# NIBB.net
KiCad netlist of a schematic drawn in EAGLE
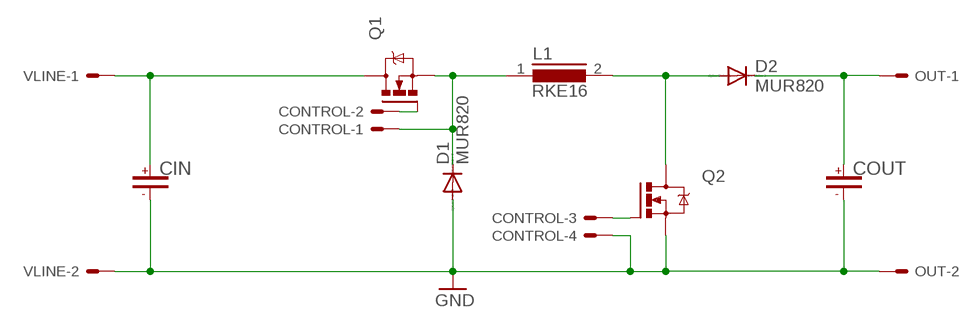
[diagram p0: schematic, sheet 1]

(export (version "E")
  (design (tool "Eeschema 10.0.6"))
  (components
    (comp (ref "CIN")
      (value "CAPP-UF")
      (footprint "eagle-import:20ROUND40P")
      (libsource (lib "eagle-import") (part "CAPP-UF"))
    )
    (comp (ref "CONTROL")
      (value "22-23-2041")
      (footprint "eagle-import:22-23-2041")
      (fields (field (name "MF") "MOLEX"))
      (libsource (lib "eagle-import") (part "22-23-2041"))
    )
    (comp (ref "COUT")
      (value "CAPP-UF")
      (footprint "eagle-import:20ROUND40P")
      (libsource (lib "eagle-import") (part "CAPP-UF"))
    )
    (comp (ref "D1")
      (value "MUR820")
      (footprint "eagle-import:C221B1A")
      (libsource (lib "eagle-import") (part "MUR820"))
    )
    (comp (ref "D2")
      (value "MUR820")
      (footprint "eagle-import:C221B1A")
      (libsource (lib "eagle-import") (part "MUR820"))
    )
    (comp (ref "L1")
      (value "RKE16")
      (footprint "eagle-import:RKE16")
      (libsource (lib "eagle-import") (part "RKE16"))
    )
    (comp (ref "OUT")
      (value "22-23-2021")
      (footprint "eagle-import:22-23-2021")
      (fields (field (name "MF") "MOLEX"))
      (libsource (lib "eagle-import") (part "22-23-2021"))
    )
    (comp (ref "Q1")
      (value "IRF640")
      (footprint "eagle-import:TO220BV")
      (libsource (lib "eagle-import") (part "IRF640"))
    )
    (comp (ref "Q2")
      (value "IRF640")
      (footprint "eagle-import:TO220BV")
      (libsource (lib "eagle-import") (part "IRF640"))
    )
    (comp (ref "VLINE")
      (value "22-23-2021")
      (footprint "eagle-import:22-23-2021")
      (fields (field (name "MF") "MOLEX"))
      (libsource (lib "eagle-import") (part "22-23-2021"))
    )
  )
  (nets
    (net (code "1") (name "GND") (class "Default")
      (node (ref "CIN") (pin "-") (pinfunction "-_-") (pintype "passive"))
      (node (ref "CONTROL") (pin "4") (pinfunction "S_4") (pintype "passive"))
      (node (ref "COUT") (pin "-") (pinfunction "-_-") (pintype "passive"))
      (node (ref "D1") (pin "A") (pinfunction "A_A") (pintype "passive"))
      (node (ref "OUT") (pin "2") (pinfunction "S_2") (pintype "passive"))
      (node (ref "Q2") (pin "S") (pinfunction "S_S") (pintype "passive"))
      (node (ref "VLINE") (pin "2") (pinfunction "S_2") (pintype "passive"))
    )
    (net (code "2") (name "Net-(CONTROLA-S)") (class "Default")
      (node (ref "CONTROL") (pin "1") (pinfunction "S_1") (pintype "passive"))
      (node (ref "D1") (pin "C") (pinfunction "C_C") (pintype "passive"))
      (node (ref "L1") (pin "1") (pinfunction "1_1") (pintype "passive"))
      (node (ref "Q1") (pin "S") (pinfunction "S_S") (pintype "passive"))
    )
    (net (code "3") (name "Net-(CONTROLB-S)") (class "Default")
      (node (ref "CONTROL") (pin "2") (pinfunction "S_2") (pintype "passive"))
      (node (ref "Q1") (pin "G") (pinfunction "G_G") (pintype "passive"))
    )
    (net (code "4") (name "Net-(CONTROLC-S)") (class "Default")
      (node (ref "CONTROL") (pin "3") (pinfunction "S_3") (pintype "passive"))
      (node (ref "Q2") (pin "G") (pinfunction "G_G") (pintype "passive"))
    )
    (net (code "5") (name "Net-(D2-PadA)") (class "Default")
      (node (ref "D2") (pin "A") (pinfunction "A_A") (pintype "passive"))
      (node (ref "L1") (pin "2") (pinfunction "2_2") (pintype "passive"))
      (node (ref "Q2") (pin "D") (pinfunction "D_D") (pintype "passive"))
    )
    (net (code "6") (name "Net-(OUTA-S)") (class "Default")
      (node (ref "COUT") (pin "+") (pinfunction "+_+") (pintype "passive"))
      (node (ref "D2") (pin "C") (pinfunction "C_C") (pintype "passive"))
      (node (ref "OUT") (pin "1") (pinfunction "S_1") (pintype "passive"))
    )
    (net (code "7") (name "Net-(VLINEA-S)") (class "Default")
      (node (ref "CIN") (pin "+") (pinfunction "+_+") (pintype "passive"))
      (node (ref "Q1") (pin "D") (pinfunction "D_D") (pintype "passive"))
      (node (ref "VLINE") (pin "1") (pinfunction "S_1") (pintype "passive"))
    )
  )
)
